# microcpu-1line-try1.net
KiCad netlist of a schematic drawn in EAGLE
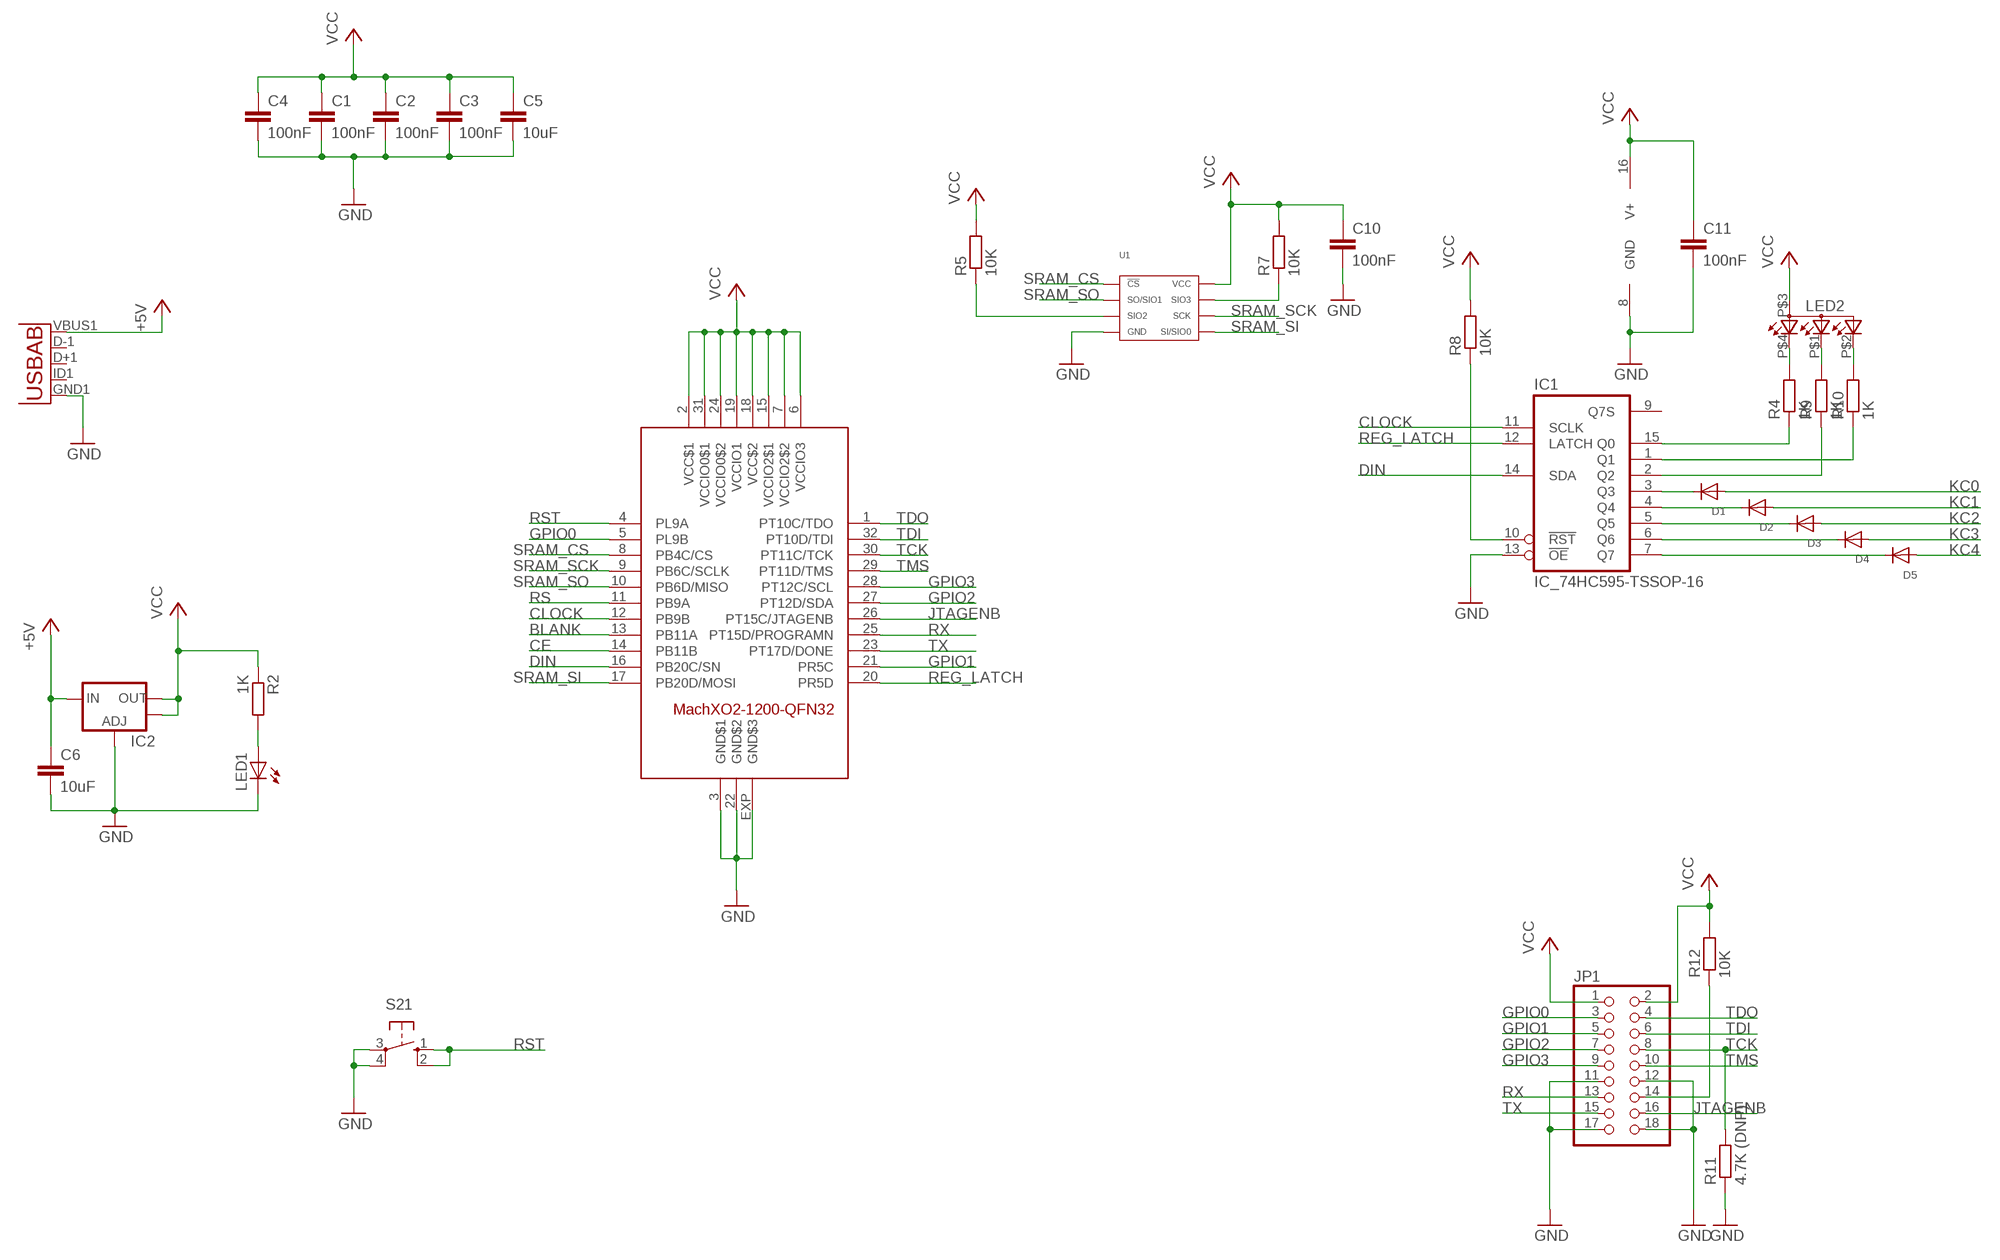
[diagram p0: schematic, sheet 1]
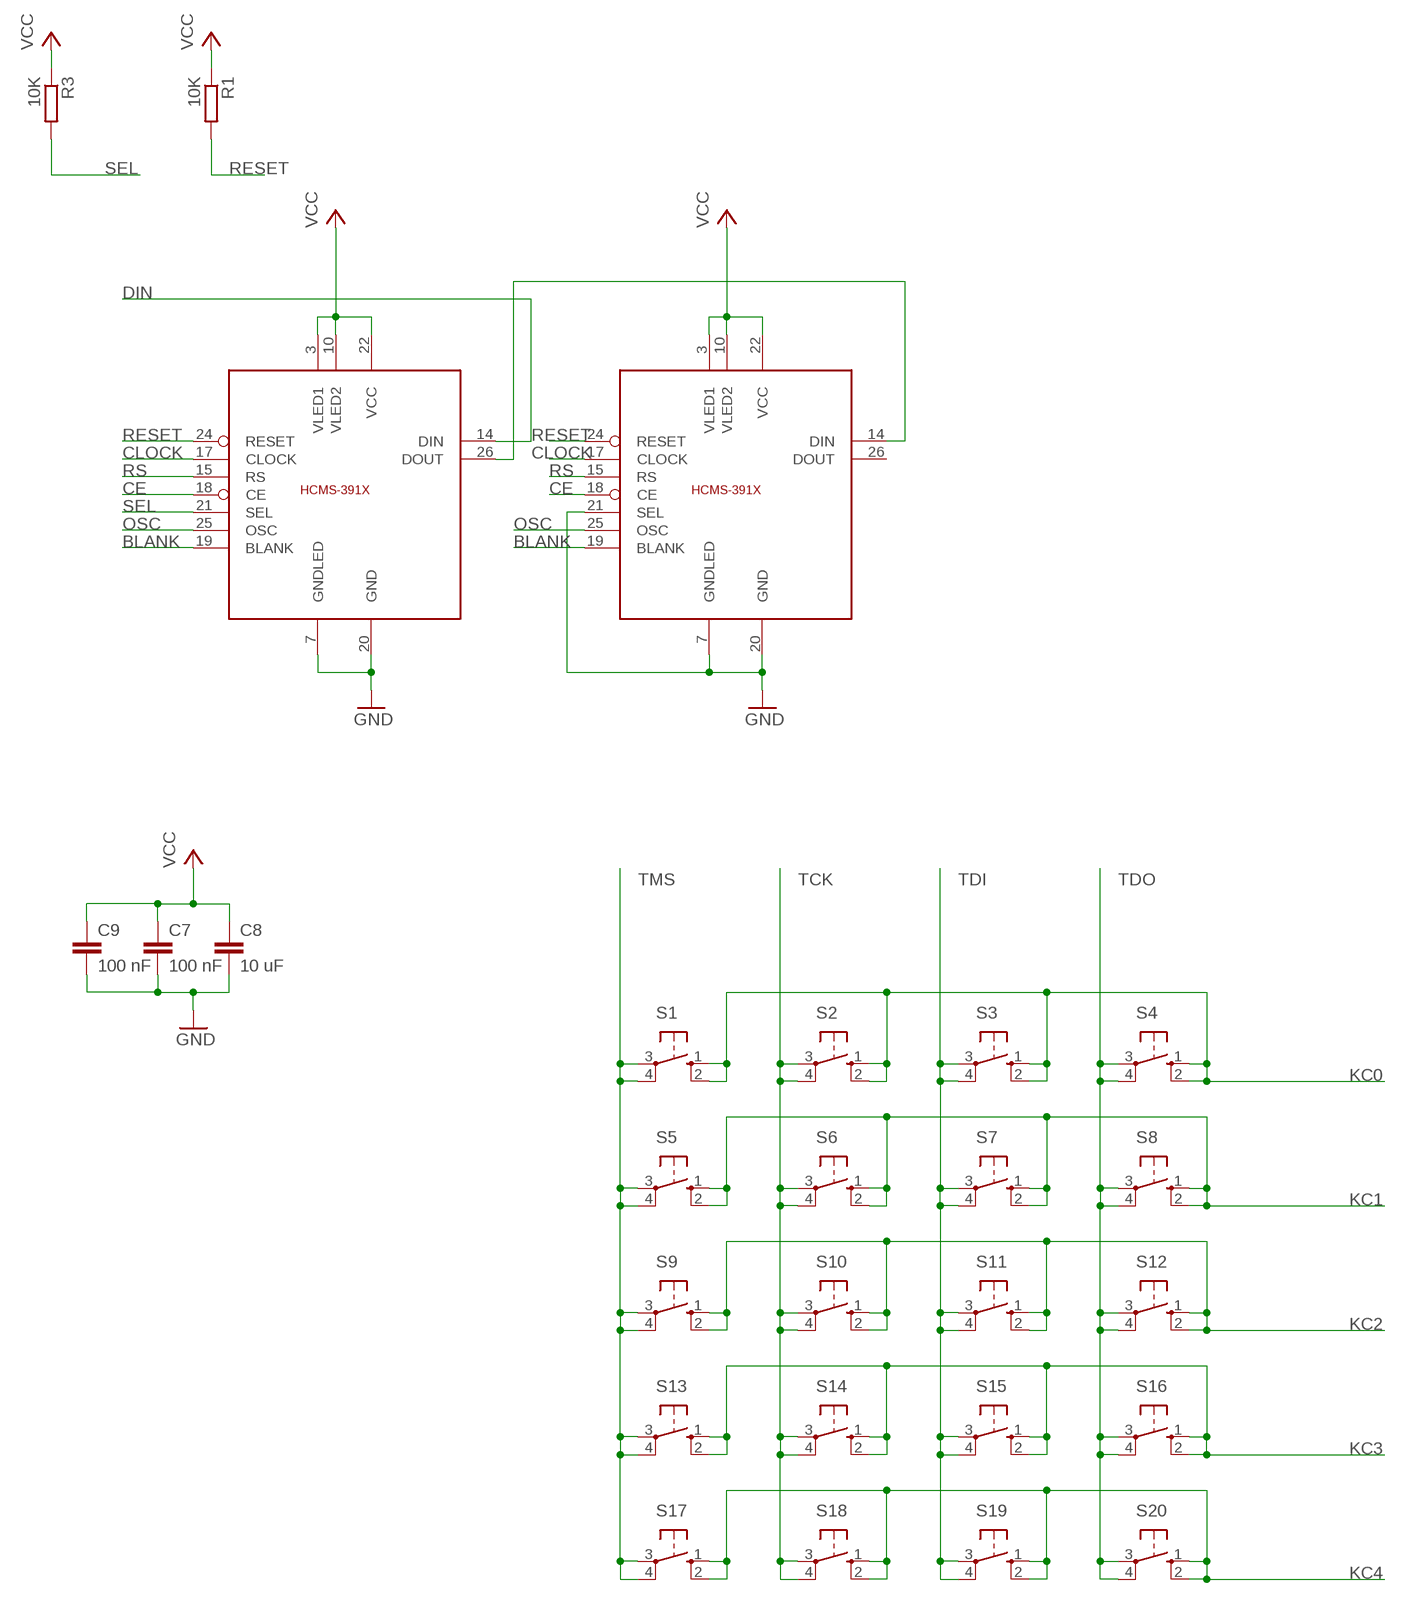
[diagram p1: schematic, sheet 2]

(export (version "E")
  (design (tool "Eeschema 10.0.6"))
  (components
    (comp (ref "C1")
      (value "100nF")
      (footprint "eagle-import:C0603")
      (libsource (lib "eagle-import") (part "resistor_348_C-EUC0603"))
    )
    (comp (ref "C2")
      (value "100nF")
      (footprint "eagle-import:C0603")
      (libsource (lib "eagle-import") (part "resistor_348_C-EUC0603"))
    )
    (comp (ref "C3")
      (value "100nF")
      (footprint "eagle-import:C0603")
      (libsource (lib "eagle-import") (part "resistor_348_C-EUC0603"))
    )
    (comp (ref "C4")
      (value "100nF")
      (footprint "eagle-import:C0603")
      (libsource (lib "eagle-import") (part "resistor_348_C-EUC0603"))
    )
    (comp (ref "C5")
      (value "10uF")
      (footprint "eagle-import:C0805")
      (libsource (lib "eagle-import") (part "resistor_348_C-EUC0805"))
    )
    (comp (ref "C6")
      (value "10uF")
      (footprint "eagle-import:C0805")
      (libsource (lib "eagle-import") (part "resistor_348_C-EUC0805"))
    )
    (comp (ref "C10")
      (value "100nF")
      (footprint "eagle-import:C0603")
      (libsource (lib "eagle-import") (part "resistor_348_C-EUC0603"))
    )
    (comp (ref "C11")
      (value "100nF")
      (footprint "eagle-import:C0603")
      (libsource (lib "eagle-import") (part "resistor_348_C-EUC0603"))
    )
    (comp (ref "D1")
      (value "DIODESOD-123")
      (footprint "eagle-import:SOD-123")
      (libsource (lib "eagle-import") (part "DIODESOD-123"))
    )
    (comp (ref "D2")
      (value "DIODESOD-123")
      (footprint "eagle-import:SOD-123")
      (libsource (lib "eagle-import") (part "DIODESOD-123"))
    )
    (comp (ref "D3")
      (value "DIODESOD-123")
      (footprint "eagle-import:SOD-123")
      (libsource (lib "eagle-import") (part "DIODESOD-123"))
    )
    (comp (ref "D4")
      (value "DIODESOD-123")
      (footprint "eagle-import:SOD-123")
      (libsource (lib "eagle-import") (part "DIODESOD-123"))
    )
    (comp (ref "D5")
      (value "DIODESOD-123")
      (footprint "eagle-import:SOD-123")
      (libsource (lib "eagle-import") (part "DIODESOD-123"))
    )
    (comp (ref "IC1")
      (value "IC_74HC595-TSSOP-16")
      (footprint "eagle-import:TSSOP-16")
      (libsource (lib "eagle-import") (part "IC_74HC595-TSSOP-16"))
    )
    (comp (ref "IC2")
      (value "V_REG_LM1117SOT223")
      (footprint "eagle-import:SOT223")
      (libsource (lib "eagle-import") (part "V_REG_LM1117SOT223"))
    )
    (comp (ref "JP1")
      (value "PINHD-2X9/90")
      (footprint "eagle-import:2X09_90")
      (libsource (lib "eagle-import") (part "PINHD-2X9/90"))
    )
    (comp (ref "LED1")
      (value "LEDCHIPLED_0603")
      (footprint "eagle-import:CHIPLED_0603")
      (libsource (lib "eagle-import") (part "LEDCHIPLED_0603"))
    )
    (comp (ref "LED2")
      (value "19-237/R6GHBHC-A04/2T")
      (footprint "eagle-import:19-237_R6GHBHC-A04_2T")
      (libsource (lib "eagle-import") (part "19-237/R6GHBHC-A04/2T"))
    )
    (comp (ref "R2")
      (value "1K")
      (footprint "eagle-import:R0603")
      (libsource (lib "eagle-import") (part "R-EU_R0603"))
    )
    (comp (ref "R4")
      (value "1K")
      (footprint "eagle-import:R0603")
      (libsource (lib "eagle-import") (part "R-EU_R0603"))
    )
    (comp (ref "R5")
      (value "10K")
      (footprint "eagle-import:R0603")
      (libsource (lib "eagle-import") (part "R-EU_R0603"))
    )
    (comp (ref "R7")
      (value "10K")
      (footprint "eagle-import:R0603")
      (libsource (lib "eagle-import") (part "R-EU_R0603"))
    )
    (comp (ref "R8")
      (value "10K")
      (footprint "eagle-import:R0603")
      (libsource (lib "eagle-import") (part "R-EU_R0603"))
    )
    (comp (ref "R9")
      (value "1K")
      (footprint "eagle-import:R0603")
      (libsource (lib "eagle-import") (part "R-EU_R0603"))
    )
    (comp (ref "R10")
      (value "1K")
      (footprint "eagle-import:R0603")
      (libsource (lib "eagle-import") (part "R-EU_R0603"))
    )
    (comp (ref "R11")
      (value "4.7K (DNP)")
      (footprint "eagle-import:R0603")
      (libsource (lib "eagle-import") (part "R-EU_R0603"))
    )
    (comp (ref "R12")
      (value "10K")
      (footprint "eagle-import:R0603")
      (libsource (lib "eagle-import") (part "R-EU_R0603"))
    )
    (comp (ref "S21")
      (value "10-XX")
      (footprint "eagle-import:B3F-10XX")
      (fields (field (name "MPN") "B3F-1000"))
      (libsource (lib "eagle-import") (part "10-XX"))
    )
    (comp (ref "U$1")
      (value "MACHXO2-1200")
      (footprint "eagle-import:QFN32")
      (libsource (lib "eagle-import") (part "MACHXO2-1200"))
    )
    (comp (ref "U1")
      (value "23A1024/23LC1024-I/SN")
      (footprint "eagle-import:23A1024_SOIC-8")
      (libsource (lib "eagle-import") (part "23A1024/23LC1024-I/SN"))
    )
    (comp (ref "U2")
      (value "USB\"\"")
      (footprint "eagle-import:USB-MICRO-SMD")
      (libsource (lib "eagle-import") (part "USB{dblquote}{dblquote}"))
    )
    (comp (ref "C7")
      (value "100 nF")
      (footprint "eagle-import:C0603K")
      (libsource (lib "eagle-import") (part "resistor_348_C-EUC0603K"))
    )
    (comp (ref "C8")
      (value "10 uF")
      (footprint "eagle-import:C0805K")
      (libsource (lib "eagle-import") (part "C-EUC0805K"))
    )
    (comp (ref "C9")
      (value "100 nF")
      (footprint "eagle-import:C0603K")
      (libsource (lib "eagle-import") (part "resistor_348_C-EUC0603K"))
    )
    (comp (ref "R1")
      (value "10K")
      (footprint "eagle-import:R0603")
      (libsource (lib "eagle-import") (part "R-EU_R0603"))
    )
    (comp (ref "R3")
      (value "10K")
      (footprint "eagle-import:R0603")
      (libsource (lib "eagle-import") (part "R-EU_R0603"))
    )
    (comp (ref "S1")
      (value "10-XX")
      (footprint "eagle-import:B3F-10XX")
      (fields (field (name "MPN") "B3F-1000"))
      (libsource (lib "eagle-import") (part "10-XX"))
    )
    (comp (ref "S2")
      (value "10-XX")
      (footprint "eagle-import:B3F-10XX")
      (fields (field (name "MPN") "B3F-1000"))
      (libsource (lib "eagle-import") (part "10-XX"))
    )
    (comp (ref "S3")
      (value "10-XX")
      (footprint "eagle-import:B3F-10XX")
      (fields (field (name "MPN") "B3F-1000"))
      (libsource (lib "eagle-import") (part "10-XX"))
    )
    (comp (ref "S4")
      (value "10-XX")
      (footprint "eagle-import:B3F-10XX")
      (fields (field (name "MPN") "B3F-1000"))
      (libsource (lib "eagle-import") (part "10-XX"))
    )
    (comp (ref "S5")
      (value "10-XX")
      (footprint "eagle-import:B3F-10XX")
      (fields (field (name "MPN") "B3F-1000"))
      (libsource (lib "eagle-import") (part "10-XX"))
    )
    (comp (ref "S6")
      (value "10-XX")
      (footprint "eagle-import:B3F-10XX")
      (fields (field (name "MPN") "B3F-1000"))
      (libsource (lib "eagle-import") (part "10-XX"))
    )
    (comp (ref "S7")
      (value "10-XX")
      (footprint "eagle-import:B3F-10XX")
      (fields (field (name "MPN") "B3F-1000"))
      (libsource (lib "eagle-import") (part "10-XX"))
    )
    (comp (ref "S8")
      (value "10-XX")
      (footprint "eagle-import:B3F-10XX")
      (fields (field (name "MPN") "B3F-1000"))
      (libsource (lib "eagle-import") (part "10-XX"))
    )
    (comp (ref "S9")
      (value "10-XX")
      (footprint "eagle-import:B3F-10XX")
      (fields (field (name "MPN") "B3F-1000"))
      (libsource (lib "eagle-import") (part "10-XX"))
    )
    (comp (ref "S10")
      (value "10-XX")
      (footprint "eagle-import:B3F-10XX")
      (fields (field (name "MPN") "B3F-1000"))
      (libsource (lib "eagle-import") (part "10-XX"))
    )
    (comp (ref "S11")
      (value "10-XX")
      (footprint "eagle-import:B3F-10XX")
      (fields (field (name "MPN") "B3F-1000"))
      (libsource (lib "eagle-import") (part "10-XX"))
    )
    (comp (ref "S12")
      (value "10-XX")
      (footprint "eagle-import:B3F-10XX")
      (fields (field (name "MPN") "B3F-1000"))
      (libsource (lib "eagle-import") (part "10-XX"))
    )
    (comp (ref "S13")
      (value "10-XX")
      (footprint "eagle-import:B3F-10XX")
      (fields (field (name "MPN") "B3F-1000"))
      (libsource (lib "eagle-import") (part "10-XX"))
    )
    (comp (ref "S14")
      (value "10-XX")
      (footprint "eagle-import:B3F-10XX")
      (fields (field (name "MPN") "B3F-1000"))
      (libsource (lib "eagle-import") (part "10-XX"))
    )
    (comp (ref "S15")
      (value "10-XX")
      (footprint "eagle-import:B3F-10XX")
      (fields (field (name "MPN") "B3F-1000"))
      (libsource (lib "eagle-import") (part "10-XX"))
    )
    (comp (ref "S16")
      (value "10-XX")
      (footprint "eagle-import:B3F-10XX")
      (fields (field (name "MPN") "B3F-1000"))
      (libsource (lib "eagle-import") (part "10-XX"))
    )
    (comp (ref "S17")
      (value "10-XX")
      (footprint "eagle-import:B3F-10XX")
      (fields (field (name "MPN") "B3F-1000"))
      (libsource (lib "eagle-import") (part "10-XX"))
    )
    (comp (ref "S18")
      (value "10-XX")
      (footprint "eagle-import:B3F-10XX")
      (fields (field (name "MPN") "B3F-1000"))
      (libsource (lib "eagle-import") (part "10-XX"))
    )
    (comp (ref "S19")
      (value "10-XX")
      (footprint "eagle-import:B3F-10XX")
      (fields (field (name "MPN") "B3F-1000"))
      (libsource (lib "eagle-import") (part "10-XX"))
    )
    (comp (ref "S20")
      (value "10-XX")
      (footprint "eagle-import:B3F-10XX")
      (fields (field (name "MPN") "B3F-1000"))
      (libsource (lib "eagle-import") (part "10-XX"))
    )
    (comp (ref "U$2")
      (value "HCMS-391X")
      (footprint "eagle-import:HCMS-391X")
      (libsource (lib "eagle-import") (part "HCMS-391X"))
    )
    (comp (ref "U$3")
      (value "HCMS-391X")
      (footprint "eagle-import:HCMS-391X")
      (libsource (lib "eagle-import") (part "HCMS-391X"))
    )
  )
  (nets
    (net (code "1") (name "+5V") (class "Default")
      (node (ref "C6") (pin "1") (pinfunction "1_1") (pintype "passive"))
      (node (ref "IC2") (pin "3") (pinfunction "IN_3") (pintype "input"))
      (node (ref "U2") (pin "VBUS1") (pinfunction "VBUS_VBUS1") (pintype "bidirectional"))
    )
    (net (code "2") (name "BLANK") (class "Default")
      (node (ref "U$1") (pin "13") (pinfunction "PB11A_13") (pintype "bidirectional"))
      (node (ref "U$2") (pin "19") (pinfunction "BLANK_19") (pintype "input"))
      (node (ref "U$3") (pin "19") (pinfunction "BLANK_19") (pintype "input"))
    )
    (net (code "3") (name "CE") (class "Default")
      (node (ref "U$1") (pin "14") (pinfunction "PB11B_14") (pintype "bidirectional"))
      (node (ref "U$2") (pin "18") (pinfunction "CE_18") (pintype "input"))
      (node (ref "U$3") (pin "18") (pinfunction "CE_18") (pintype "input"))
    )
    (net (code "4") (name "CLOCK") (class "Default")
      (node (ref "IC1") (pin "11") (pinfunction "SCLK_11") (pintype "input"))
      (node (ref "U$1") (pin "12") (pinfunction "PB9B_12") (pintype "bidirectional"))
      (node (ref "U$2") (pin "17") (pinfunction "CLOCK_17") (pintype "input"))
      (node (ref "U$3") (pin "17") (pinfunction "CLOCK_17") (pintype "input"))
    )
    (net (code "5") (name "DIN") (class "Default")
      (node (ref "IC1") (pin "14") (pinfunction "SDA_14") (pintype "input"))
      (node (ref "U$1") (pin "16") (pinfunction "PB20C/SN_16") (pintype "bidirectional"))
      (node (ref "U$2") (pin "14") (pinfunction "DIN_14") (pintype "input"))
    )
    (net (code "6") (name "GND") (class "Default")
      (node (ref "C1") (pin "2") (pinfunction "2_2") (pintype "passive"))
      (node (ref "C10") (pin "2") (pinfunction "2_2") (pintype "passive"))
      (node (ref "C11") (pin "2") (pinfunction "2_2") (pintype "passive"))
      (node (ref "C2") (pin "2") (pinfunction "2_2") (pintype "passive"))
      (node (ref "C3") (pin "2") (pinfunction "2_2") (pintype "passive"))
      (node (ref "C4") (pin "2") (pinfunction "2_2") (pintype "passive"))
      (node (ref "C5") (pin "2") (pinfunction "2_2") (pintype "passive"))
      (node (ref "C6") (pin "2") (pinfunction "2_2") (pintype "passive"))
      (node (ref "C7") (pin "2") (pinfunction "2_2") (pintype "passive"))
      (node (ref "C8") (pin "2") (pinfunction "2_2") (pintype "passive"))
      (node (ref "C9") (pin "2") (pinfunction "2_2") (pintype "passive"))
      (node (ref "IC1") (pin "13") (pinfunction "~{OE}_13") (pintype "input"))
      (node (ref "IC1") (pin "8") (pinfunction "GND_8") (pintype "power_in"))
      (node (ref "IC2") (pin "1") (pinfunction "ADJ_1") (pintype "input"))
      (node (ref "JP1") (pin "11") (pinfunction "11_11") (pintype "passive"))
      (node (ref "JP1") (pin "12") (pinfunction "12_12") (pintype "passive"))
      (node (ref "JP1") (pin "17") (pinfunction "17_17") (pintype "passive"))
      (node (ref "JP1") (pin "18") (pinfunction "18_18") (pintype "passive"))
      (node (ref "LED1") (pin "C") (pinfunction "C_C") (pintype "passive"))
      (node (ref "R11") (pin "1") (pinfunction "1_1") (pintype "passive"))
      (node (ref "S21") (pin "3") (pinfunction "P_3") (pintype "passive"))
      (node (ref "S21") (pin "4") (pinfunction "P1_4") (pintype "passive"))
      (node (ref "U$1") (pin "22") (pinfunction "GND$2_22") (pintype "power_in"))
      (node (ref "U$1") (pin "3") (pinfunction "GND$1_3") (pintype "power_in"))
      (node (ref "U$1") (pin "EXP") (pinfunction "GND$3_EXP") (pintype "power_in"))
      (node (ref "U$2") (pin "20") (pinfunction "GND_20") (pintype "power_in"))
      (node (ref "U$2") (pin "7") (pinfunction "GNDLED_7") (pintype "power_in"))
      (node (ref "U$3") (pin "20") (pinfunction "GND_20") (pintype "power_in"))
      (node (ref "U$3") (pin "21") (pinfunction "SEL_21") (pintype "input"))
      (node (ref "U$3") (pin "7") (pinfunction "GNDLED_7") (pintype "power_in"))
      (node (ref "U1") (pin "4") (pinfunction "GND_4") (pintype "bidirectional"))
      (node (ref "U2") (pin "GND1") (pinfunction "GND_GND1") (pintype "bidirectional"))
    )
    (net (code "7") (name "GPIO0") (class "Default")
      (node (ref "JP1") (pin "3") (pinfunction "3_3") (pintype "passive"))
      (node (ref "U$1") (pin "5") (pinfunction "PL9B_5") (pintype "bidirectional"))
    )
    (net (code "8") (name "GPIO1") (class "Default")
      (node (ref "JP1") (pin "5") (pinfunction "5_5") (pintype "passive"))
      (node (ref "U$1") (pin "21") (pinfunction "PR5C_21") (pintype "bidirectional"))
    )
    (net (code "9") (name "GPIO2") (class "Default")
      (node (ref "JP1") (pin "7") (pinfunction "7_7") (pintype "passive"))
      (node (ref "U$1") (pin "27") (pinfunction "PT12D/SDA_27") (pintype "bidirectional"))
    )
    (net (code "10") (name "GPIO3") (class "Default")
      (node (ref "JP1") (pin "9") (pinfunction "9_9") (pintype "passive"))
      (node (ref "U$1") (pin "28") (pinfunction "PT12C/SCL_28") (pintype "bidirectional"))
    )
    (net (code "11") (name "JTAGENB") (class "Default")
      (node (ref "JP1") (pin "16") (pinfunction "16_16") (pintype "passive"))
      (node (ref "U$1") (pin "26") (pinfunction "PT15C/JTAGENB_26") (pintype "bidirectional"))
    )
    (net (code "12") (name "KC0") (class "Default")
      (node (ref "D1") (pin "A") (pinfunction "A_A") (pintype "passive"))
      (node (ref "S1") (pin "1") (pinfunction "S_1") (pintype "passive"))
      (node (ref "S1") (pin "2") (pinfunction "S1_2") (pintype "passive"))
      (node (ref "S2") (pin "1") (pinfunction "S_1") (pintype "passive"))
      (node (ref "S2") (pin "2") (pinfunction "S1_2") (pintype "passive"))
      (node (ref "S3") (pin "1") (pinfunction "S_1") (pintype "passive"))
      (node (ref "S3") (pin "2") (pinfunction "S1_2") (pintype "passive"))
      (node (ref "S4") (pin "1") (pinfunction "S_1") (pintype "passive"))
      (node (ref "S4") (pin "2") (pinfunction "S1_2") (pintype "passive"))
    )
    (net (code "13") (name "KC1") (class "Default")
      (node (ref "D2") (pin "A") (pinfunction "A_A") (pintype "passive"))
      (node (ref "S5") (pin "1") (pinfunction "S_1") (pintype "passive"))
      (node (ref "S5") (pin "2") (pinfunction "S1_2") (pintype "passive"))
      (node (ref "S6") (pin "1") (pinfunction "S_1") (pintype "passive"))
      (node (ref "S6") (pin "2") (pinfunction "S1_2") (pintype "passive"))
      (node (ref "S7") (pin "1") (pinfunction "S_1") (pintype "passive"))
      (node (ref "S7") (pin "2") (pinfunction "S1_2") (pintype "passive"))
      (node (ref "S8") (pin "1") (pinfunction "S_1") (pintype "passive"))
      (node (ref "S8") (pin "2") (pinfunction "S1_2") (pintype "passive"))
    )
    (net (code "14") (name "KC2") (class "Default")
      (node (ref "D3") (pin "A") (pinfunction "A_A") (pintype "passive"))
      (node (ref "S10") (pin "1") (pinfunction "S_1") (pintype "passive"))
      (node (ref "S10") (pin "2") (pinfunction "S1_2") (pintype "passive"))
      (node (ref "S11") (pin "1") (pinfunction "S_1") (pintype "passive"))
      (node (ref "S11") (pin "2") (pinfunction "S1_2") (pintype "passive"))
      (node (ref "S12") (pin "1") (pinfunction "S_1") (pintype "passive"))
      (node (ref "S12") (pin "2") (pinfunction "S1_2") (pintype "passive"))
      (node (ref "S9") (pin "1") (pinfunction "S_1") (pintype "passive"))
      (node (ref "S9") (pin "2") (pinfunction "S1_2") (pintype "passive"))
    )
    (net (code "15") (name "KC3") (class "Default")
      (node (ref "D4") (pin "A") (pinfunction "A_A") (pintype "passive"))
      (node (ref "S13") (pin "1") (pinfunction "S_1") (pintype "passive"))
      (node (ref "S13") (pin "2") (pinfunction "S1_2") (pintype "passive"))
      (node (ref "S14") (pin "1") (pinfunction "S_1") (pintype "passive"))
      (node (ref "S14") (pin "2") (pinfunction "S1_2") (pintype "passive"))
      (node (ref "S15") (pin "1") (pinfunction "S_1") (pintype "passive"))
      (node (ref "S15") (pin "2") (pinfunction "S1_2") (pintype "passive"))
      (node (ref "S16") (pin "1") (pinfunction "S_1") (pintype "passive"))
      (node (ref "S16") (pin "2") (pinfunction "S1_2") (pintype "passive"))
    )
    (net (code "16") (name "KC4") (class "Default")
      (node (ref "D5") (pin "A") (pinfunction "A_A") (pintype "passive"))
      (node (ref "S17") (pin "1") (pinfunction "S_1") (pintype "passive"))
      (node (ref "S17") (pin "2") (pinfunction "S1_2") (pintype "passive"))
      (node (ref "S18") (pin "1") (pinfunction "S_1") (pintype "passive"))
      (node (ref "S18") (pin "2") (pinfunction "S1_2") (pintype "passive"))
      (node (ref "S19") (pin "1") (pinfunction "S_1") (pintype "passive"))
      (node (ref "S19") (pin "2") (pinfunction "S1_2") (pintype "passive"))
      (node (ref "S20") (pin "1") (pinfunction "S_1") (pintype "passive"))
      (node (ref "S20") (pin "2") (pinfunction "S1_2") (pintype "passive"))
    )
    (net (code "17") (name "Net-(IC1A-Q0)") (class "Default")
      (node (ref "IC1") (pin "15") (pinfunction "Q0_15") (pintype "output"))
      (node (ref "R4") (pin "1") (pinfunction "1_1") (pintype "passive"))
    )
    (net (code "18") (name "Net-(IC1A-Q1)") (class "Default")
      (node (ref "IC1") (pin "1") (pinfunction "Q1_1") (pintype "output"))
      (node (ref "R10") (pin "1") (pinfunction "1_1") (pintype "passive"))
    )
    (net (code "19") (name "Net-(IC1A-Q2)") (class "Default")
      (node (ref "IC1") (pin "2") (pinfunction "Q2_2") (pintype "output"))
      (node (ref "R9") (pin "1") (pinfunction "1_1") (pintype "passive"))
    )
    (net (code "20") (name "Net-(IC1A-Q3)") (class "Default")
      (node (ref "D1") (pin "C") (pinfunction "C_C") (pintype "passive"))
      (node (ref "IC1") (pin "3") (pinfunction "Q3_3") (pintype "output"))
    )
    (net (code "21") (name "Net-(IC1A-Q4)") (class "Default")
      (node (ref "D2") (pin "C") (pinfunction "C_C") (pintype "passive"))
      (node (ref "IC1") (pin "4") (pinfunction "Q4_4") (pintype "output"))
    )
    (net (code "22") (name "Net-(IC1A-Q5)") (class "Default")
      (node (ref "D3") (pin "C") (pinfunction "C_C") (pintype "passive"))
      (node (ref "IC1") (pin "5") (pinfunction "Q5_5") (pintype "output"))
    )
    (net (code "23") (name "Net-(IC1A-Q6)") (class "Default")
      (node (ref "D4") (pin "C") (pinfunction "C_C") (pintype "passive"))
      (node (ref "IC1") (pin "6") (pinfunction "Q6_6") (pintype "output"))
    )
    (net (code "24") (name "Net-(IC1A-Q7)") (class "Default")
      (node (ref "D5") (pin "C") (pinfunction "C_C") (pintype "passive"))
      (node (ref "IC1") (pin "7") (pinfunction "Q7_7") (pintype "output"))
    )
    (net (code "25") (name "Net-(IC1A-~{RST})") (class "Default")
      (node (ref "IC1") (pin "10") (pinfunction "~{RST}_10") (pintype "input"))
      (node (ref "R8") (pin "1") (pinfunction "1_1") (pintype "passive"))
    )
    (net (code "26") (name "Net-(JP1-Pad14)") (class "Default")
      (node (ref "JP1") (pin "14") (pinfunction "14_14") (pintype "passive"))
      (node (ref "R12") (pin "1") (pinfunction "1_1") (pintype "passive"))
    )
    (net (code "27") (name "Net-(LED1-PadA)") (class "Default")
      (node (ref "LED1") (pin "A") (pinfunction "A_A") (pintype "passive"))
      (node (ref "R2") (pin "2") (pinfunction "2_2") (pintype "passive"))
    )
    (net (code "28") (name "Net-(LED2-CBLUE)") (class "Default")
      (node (ref "LED2") (pin "P$1") (pinfunction "CBLUE_P$1") (pintype "passive"))
      (node (ref "R9") (pin "2") (pinfunction "2_2") (pintype "passive"))
    )
    (net (code "29") (name "Net-(LED2-CGREEN)") (class "Default")
      (node (ref "LED2") (pin "P$2") (pinfunction "CGREEN_P$2") (pintype "passive"))
      (node (ref "R10") (pin "2") (pinfunction "2_2") (pintype "passive"))
    )
    (net (code "30") (name "Net-(LED2-CRED)") (class "Default")
      (node (ref "LED2") (pin "P$4") (pinfunction "CRED_P$4") (pintype "passive"))
      (node (ref "R4") (pin "2") (pinfunction "2_2") (pintype "passive"))
    )
    (net (code "31") (name "Net-(U$2-DOUT)") (class "Default")
      (node (ref "U$2") (pin "26") (pinfunction "DOUT_26") (pintype "output"))
      (node (ref "U$3") (pin "14") (pinfunction "DIN_14") (pintype "input"))
    )
    (net (code "32") (name "Net-(U1-SIO2)") (class "Default")
      (node (ref "R5") (pin "1") (pinfunction "1_1") (pintype "passive"))
      (node (ref "U1") (pin "3") (pinfunction "SIO2_3") (pintype "bidirectional"))
    )
    (net (code "33") (name "Net-(U1-SIO3)") (class "Default")
      (node (ref "R7") (pin "1") (pinfunction "1_1") (pintype "passive"))
      (node (ref "U1") (pin "7") (pinfunction "SIO3_7") (pintype "bidirectional"))
    )
    (net (code "34") (name "OSC") (class "Default")
      (node (ref "U$2") (pin "25") (pinfunction "OSC_25") (pintype "bidirectional"))
      (node (ref "U$3") (pin "25") (pinfunction "OSC_25") (pintype "bidirectional"))
    )
    (net (code "35") (name "REG_LATCH") (class "Default")
      (node (ref "IC1") (pin "12") (pinfunction "LATCH_12") (pintype "input"))
      (node (ref "U$1") (pin "20") (pinfunction "PR5D_20") (pintype "bidirectional"))
    )
    (net (code "36") (name "RESET") (class "Default")
      (node (ref "R1") (pin "2") (pinfunction "2_2") (pintype "passive"))
      (node (ref "U$2") (pin "24") (pinfunction "RESET_24") (pintype "input"))
      (node (ref "U$3") (pin "24") (pinfunction "RESET_24") (pintype "input"))
    )
    (net (code "37") (name "RS") (class "Default")
      (node (ref "U$1") (pin "11") (pinfunction "PB9A_11") (pintype "bidirectional"))
      (node (ref "U$2") (pin "15") (pinfunction "RS_15") (pintype "input"))
      (node (ref "U$3") (pin "15") (pinfunction "RS_15") (pintype "input"))
    )
    (net (code "38") (name "RST") (class "Default")
      (node (ref "S21") (pin "1") (pinfunction "S_1") (pintype "passive"))
      (node (ref "S21") (pin "2") (pinfunction "S1_2") (pintype "passive"))
      (node (ref "U$1") (pin "4") (pinfunction "PL9A_4") (pintype "bidirectional"))
    )
    (net (code "39") (name "RX") (class "Default")
      (node (ref "JP1") (pin "13") (pinfunction "13_13") (pintype "passive"))
      (node (ref "U$1") (pin "25") (pinfunction "PT15D/PROGRAMN_25") (pintype "bidirectional"))
    )
    (net (code "40") (name "SEL") (class "Default")
      (node (ref "R3") (pin "2") (pinfunction "2_2") (pintype "passive"))
      (node (ref "U$2") (pin "21") (pinfunction "SEL_21") (pintype "input"))
    )
    (net (code "41") (name "SRAM_CS") (class "Default")
      (node (ref "U$1") (pin "8") (pinfunction "PB4C/CS_8") (pintype "bidirectional"))
      (node (ref "U1") (pin "1") (pinfunction "CS'_1") (pintype "bidirectional"))
    )
    (net (code "42") (name "SRAM_SCK") (class "Default")
      (node (ref "U$1") (pin "9") (pinfunction "PB6C/SCLK_9") (pintype "bidirectional"))
      (node (ref "U1") (pin "6") (pinfunction "SCK_6") (pintype "bidirectional"))
    )
    (net (code "43") (name "SRAM_SI") (class "Default")
      (node (ref "U$1") (pin "17") (pinfunction "PB20D/MOSI_17") (pintype "bidirectional"))
      (node (ref "U1") (pin "5") (pinfunction "SI/SIO0_5") (pintype "bidirectional"))
    )
    (net (code "44") (name "SRAM_SO") (class "Default")
      (node (ref "U$1") (pin "10") (pinfunction "PB6D/MISO_10") (pintype "bidirectional"))
      (node (ref "U1") (pin "2") (pinfunction "SO/SIO1_2") (pintype "bidirectional"))
    )
    (net (code "45") (name "TCK") (class "Default")
      (node (ref "JP1") (pin "8") (pinfunction "8_8") (pintype "passive"))
      (node (ref "R11") (pin "2") (pinfunction "2_2") (pintype "passive"))
      (node (ref "S10") (pin "3") (pinfunction "P_3") (pintype "passive"))
      (node (ref "S10") (pin "4") (pinfunction "P1_4") (pintype "passive"))
      (node (ref "S14") (pin "3") (pinfunction "P_3") (pintype "passive"))
      (node (ref "S14") (pin "4") (pinfunction "P1_4") (pintype "passive"))
      (node (ref "S18") (pin "3") (pinfunction "P_3") (pintype "passive"))
      (node (ref "S18") (pin "4") (pinfunction "P1_4") (pintype "passive"))
      (node (ref "S2") (pin "3") (pinfunction "P_3") (pintype "passive"))
      (node (ref "S2") (pin "4") (pinfunction "P1_4") (pintype "passive"))
      (node (ref "S6") (pin "3") (pinfunction "P_3") (pintype "passive"))
      (node (ref "S6") (pin "4") (pinfunction "P1_4") (pintype "passive"))
      (node (ref "U$1") (pin "30") (pinfunction "PT11C/TCK_30") (pintype "bidirectional"))
    )
    (net (code "46") (name "TDI") (class "Default")
      (node (ref "JP1") (pin "6") (pinfunction "6_6") (pintype "passive"))
      (node (ref "S11") (pin "3") (pinfunction "P_3") (pintype "passive"))
      (node (ref "S11") (pin "4") (pinfunction "P1_4") (pintype "passive"))
      (node (ref "S15") (pin "3") (pinfunction "P_3") (pintype "passive"))
      (node (ref "S15") (pin "4") (pinfunction "P1_4") (pintype "passive"))
      (node (ref "S19") (pin "3") (pinfunction "P_3") (pintype "passive"))
      (node (ref "S19") (pin "4") (pinfunction "P1_4") (pintype "passive"))
      (node (ref "S3") (pin "3") (pinfunction "P_3") (pintype "passive"))
      (node (ref "S3") (pin "4") (pinfunction "P1_4") (pintype "passive"))
      (node (ref "S7") (pin "3") (pinfunction "P_3") (pintype "passive"))
      (node (ref "S7") (pin "4") (pinfunction "P1_4") (pintype "passive"))
      (node (ref "U$1") (pin "32") (pinfunction "PT10D/TDI_32") (pintype "bidirectional"))
    )
    (net (code "47") (name "TDO") (class "Default")
      (node (ref "JP1") (pin "4") (pinfunction "4_4") (pintype "passive"))
      (node (ref "S12") (pin "3") (pinfunction "P_3") (pintype "passive"))
      (node (ref "S12") (pin "4") (pinfunction "P1_4") (pintype "passive"))
      (node (ref "S16") (pin "3") (pinfunction "P_3") (pintype "passive"))
      (node (ref "S16") (pin "4") (pinfunction "P1_4") (pintype "passive"))
      (node (ref "S20") (pin "3") (pinfunction "P_3") (pintype "passive"))
      (node (ref "S20") (pin "4") (pinfunction "P1_4") (pintype "passive"))
      (node (ref "S4") (pin "3") (pinfunction "P_3") (pintype "passive"))
      (node (ref "S4") (pin "4") (pinfunction "P1_4") (pintype "passive"))
      (node (ref "S8") (pin "3") (pinfunction "P_3") (pintype "passive"))
      (node (ref "S8") (pin "4") (pinfunction "P1_4") (pintype "passive"))
      (node (ref "U$1") (pin "1") (pinfunction "PT10C/TDO_1") (pintype "bidirectional"))
    )
    (net (code "48") (name "TMS") (class "Default")
      (node (ref "JP1") (pin "10") (pinfunction "10_10") (pintype "passive"))
      (node (ref "S1") (pin "3") (pinfunction "P_3") (pintype "passive"))
      (node (ref "S1") (pin "4") (pinfunction "P1_4") (pintype "passive"))
      (node (ref "S13") (pin "3") (pinfunction "P_3") (pintype "passive"))
      (node (ref "S13") (pin "4") (pinfunction "P1_4") (pintype "passive"))
      (node (ref "S17") (pin "3") (pinfunction "P_3") (pintype "passive"))
      (node (ref "S17") (pin "4") (pinfunction "P1_4") (pintype "passive"))
      (node (ref "S5") (pin "3") (pinfunction "P_3") (pintype "passive"))
      (node (ref "S5") (pin "4") (pinfunction "P1_4") (pintype "passive"))
      (node (ref "S9") (pin "3") (pinfunction "P_3") (pintype "passive"))
      (node (ref "S9") (pin "4") (pinfunction "P1_4") (pintype "passive"))
      (node (ref "U$1") (pin "29") (pinfunction "PT11D/TMS_29") (pintype "bidirectional"))
    )
    (net (code "49") (name "TX") (class "Default")
      (node (ref "JP1") (pin "15") (pinfunction "15_15") (pintype "passive"))
      (node (ref "U$1") (pin "23") (pinfunction "PT17D/DONE_23") (pintype "bidirectional"))
    )
    (net (code "50") (name "VCC") (class "Default")
      (node (ref "C1") (pin "1") (pinfunction "1_1") (pintype "passive"))
      (node (ref "C10") (pin "1") (pinfunction "1_1") (pintype "passive"))
      (node (ref "C11") (pin "1") (pinfunction "1_1") (pintype "passive"))
      (node (ref "C2") (pin "1") (pinfunction "1_1") (pintype "passive"))
      (node (ref "C3") (pin "1") (pinfunction "1_1") (pintype "passive"))
      (node (ref "C4") (pin "1") (pinfunction "1_1") (pintype "passive"))
      (node (ref "C5") (pin "1") (pinfunction "1_1") (pintype "passive"))
      (node (ref "C7") (pin "1") (pinfunction "1_1") (pintype "passive"))
      (node (ref "C8") (pin "1") (pinfunction "1_1") (pintype "passive"))
      (node (ref "C9") (pin "1") (pinfunction "1_1") (pintype "passive"))
      (node (ref "IC1") (pin "16") (pinfunction "V+_16") (pintype "power_in"))
      (node (ref "IC2") (pin "2") (pinfunction "OUT_2") (pintype "output"))
      (node (ref "IC2") (pin "4") (pinfunction "OUT_4") (pintype "output"))
      (node (ref "JP1") (pin "1") (pinfunction "1_1") (pintype "passive"))
      (node (ref "JP1") (pin "2") (pinfunction "2_2") (pintype "passive"))
      (node (ref "LED2") (pin "P$3") (pinfunction "A_P$3") (pintype "passive"))
      (node (ref "R1") (pin "1") (pinfunction "1_1") (pintype "passive"))
      (node (ref "R12") (pin "2") (pinfunction "2_2") (pintype "passive"))
      (node (ref "R2") (pin "1") (pinfunction "1_1") (pintype "passive"))
      (node (ref "R3") (pin "1") (pinfunction "1_1") (pintype "passive"))
      (node (ref "R5") (pin "2") (pinfunction "2_2") (pintype "passive"))
      (node (ref "R7") (pin "2") (pinfunction "2_2") (pintype "passive"))
      (node (ref "R8") (pin "2") (pinfunction "2_2") (pintype "passive"))
      (node (ref "U$1") (pin "15") (pinfunction "VCCIO2$1_15") (pintype "power_in"))
      (node (ref "U$1") (pin "18") (pinfunction "VCC$2_18") (pintype "power_in"))
      (node (ref "U$1") (pin "19") (pinfunction "VCCIO1_19") (pintype "power_in"))
      (node (ref "U$1") (pin "2") (pinfunction "VCC$1_2") (pintype "power_in"))
      (node (ref "U$1") (pin "24") (pinfunction "VCCIO0$2_24") (pintype "power_in"))
      (node (ref "U$1") (pin "31") (pinfunction "VCCIO0$1_31") (pintype "power_in"))
      (node (ref "U$1") (pin "6") (pinfunction "VCCIO3_6") (pintype "power_in"))
      (node (ref "U$1") (pin "7") (pinfunction "VCCIO2$2_7") (pintype "power_in"))
      (node (ref "U$2") (pin "10") (pinfunction "VLED2_10") (pintype "power_in"))
      (node (ref "U$2") (pin "22") (pinfunction "VCC_22") (pintype "power_in"))
      (node (ref "U$2") (pin "3") (pinfunction "VLED1_3") (pintype "power_in"))
      (node (ref "U$3") (pin "10") (pinfunction "VLED2_10") (pintype "power_in"))
      (node (ref "U$3") (pin "22") (pinfunction "VCC_22") (pintype "power_in"))
      (node (ref "U$3") (pin "3") (pinfunction "VLED1_3") (pintype "power_in"))
      (node (ref "U1") (pin "8") (pinfunction "VCC_8") (pintype "bidirectional"))
    )
    (net (code "51") (name "unconnected-(IC1A-Q7S-Pad9)") (class "Default")
      (node (ref "IC1") (pin "9") (pinfunction "Q7S_9") (pintype "output"))
    )
    (net (code "52") (name "unconnected-(U$3-DOUT-Pad26)") (class "Default")
      (node (ref "U$3") (pin "26") (pinfunction "DOUT_26") (pintype "output"))
    )
    (net (code "53") (name "unconnected-(U2-D+-PadD+1)") (class "Default")
      (node (ref "U2") (pin "D+1") (pinfunction "D+_D+1") (pintype "bidirectional"))
    )
    (net (code "54") (name "unconnected-(U2-D--PadD-1)") (class "Default")
      (node (ref "U2") (pin "D-1") (pinfunction "D-_D-1") (pintype "bidirectional"))
    )
    (net (code "55") (name "unconnected-(U2-USBID-PadID1)") (class "Default")
      (node (ref "U2") (pin "ID1") (pinfunction "USBID_ID1") (pintype "bidirectional"))
    )
  )
)
